# fan-shield.net
KiCad netlist of a schematic drawn in EAGLE
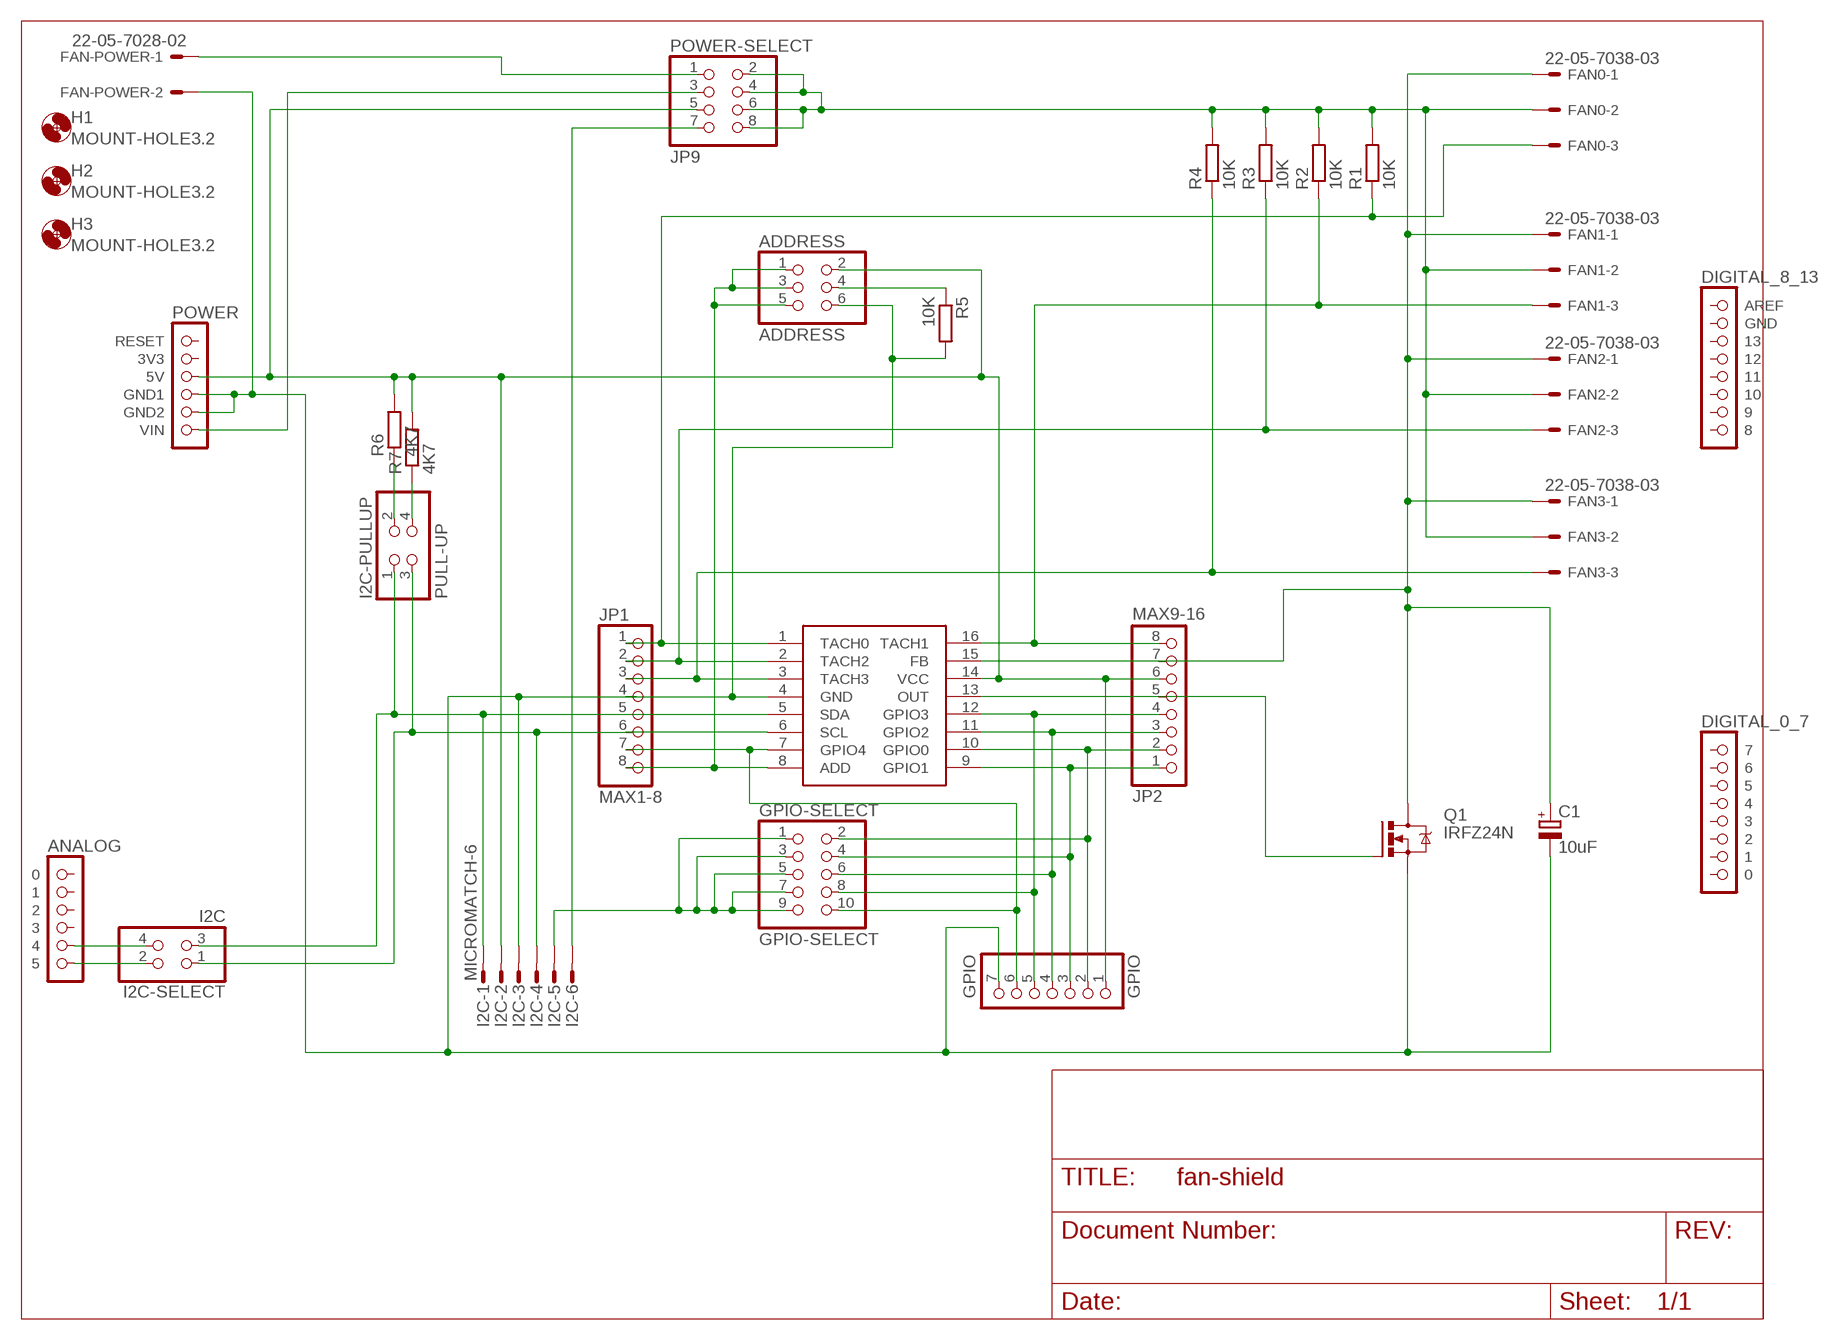
[diagram p0: schematic, sheet 1]

(export (version "E")
  (design (tool "Eeschema 10.0.6"))
  (components
    (comp (ref "ADDRESS")
      (value "ADDRESS")
      (footprint "eagle-import:2X03")
      (libsource (lib "eagle-import") (part "PINHD-2X3"))
    )
    (comp (ref "C1")
      (value "10uF")
      (footprint "eagle-import:E2,5-6")
      (libsource (lib "eagle-import") (part "CPOL-EUE2.5-6"))
    )
    (comp (ref "FAN-POWER")
      (value "22-05-7028-02")
      (footprint "eagle-import:7395-02")
      (libsource (lib "eagle-import") (part "22-?-0205-7028"))
    )
    (comp (ref "FAN0")
      (value "22-05-7038-03")
      (footprint "eagle-import:7395-03")
      (libsource (lib "eagle-import") (part "22-?-0305-7038"))
    )
    (comp (ref "FAN1")
      (value "22-05-7038-03")
      (footprint "eagle-import:7395-03")
      (libsource (lib "eagle-import") (part "22-?-0305-7038"))
    )
    (comp (ref "FAN2")
      (value "22-05-7038-03")
      (footprint "eagle-import:7395-03")
      (libsource (lib "eagle-import") (part "22-?-0305-7038"))
    )
    (comp (ref "FAN3")
      (value "22-05-7038-03")
      (footprint "eagle-import:7395-03")
      (libsource (lib "eagle-import") (part "22-?-0305-7038"))
    )
    (comp (ref "GPIO")
      (value "GPIO")
      (footprint "eagle-import:1X07_90")
      (libsource (lib "eagle-import") (part "PINHD-1X7/90"))
    )
    (comp (ref "GPIO-SELECT")
      (value "GPIO-SELECT")
      (footprint "eagle-import:2X05")
      (libsource (lib "eagle-import") (part "PINHD-2X5"))
    )
    (comp (ref "H1")
      (value "MOUNT-HOLE3.2")
      (footprint "eagle-import:3,2")
      (libsource (lib "eagle-import") (part "MOUNT-HOLE3.2"))
    )
    (comp (ref "H2")
      (value "MOUNT-HOLE3.2")
      (footprint "eagle-import:3,2")
      (libsource (lib "eagle-import") (part "MOUNT-HOLE3.2"))
    )
    (comp (ref "H3")
      (value "MOUNT-HOLE3.2")
      (footprint "eagle-import:3,2")
      (libsource (lib "eagle-import") (part "MOUNT-HOLE3.2"))
    )
    (comp (ref "I2C")
      (value "MICROMATCH-6")
      (footprint "eagle-import:MICROMATCH-6")
      (fields (field (name "MPN") "7-215464-6"))
      (libsource (lib "eagle-import") (part "MICROMATCH-6"))
    )
    (comp (ref "I2C-PULLUP")
      (value "PULL-UP")
      (footprint "eagle-import:2X02")
      (libsource (lib "eagle-import") (part "PINHD-2X2"))
    )
    (comp (ref "I2C-SELECT")
      (value "I2C")
      (footprint "eagle-import:2X02_90")
      (libsource (lib "eagle-import") (part "PINHD-2X2/90"))
    )
    (comp (ref "JP1")
      (value "MAX1-8")
      (footprint "eagle-import:1X08")
      (libsource (lib "eagle-import") (part "PINHD-1X8"))
    )
    (comp (ref "JP2")
      (value "MAX9-16")
      (footprint "eagle-import:1X08")
      (libsource (lib "eagle-import") (part "PINHD-1X8"))
    )
    (comp (ref "MAX6651")
      (value "MAX6651")
      (footprint "eagle-import:QSOP16")
      (libsource (lib "eagle-import") (part "MAX6651"))
    )
    (comp (ref "POWER-SELECT")
      (value "JP9")
      (footprint "eagle-import:2X04")
      (libsource (lib "eagle-import") (part "PINHD-2X4"))
    )
    (comp (ref "Q1")
      (value "IRFZ24N")
      (footprint "eagle-import:TO200AB")
      (libsource (lib "eagle-import") (part "IRFZ24N"))
    )
    (comp (ref "R1")
      (value "10K")
      (footprint "eagle-import:0207_10")
      (libsource (lib "eagle-import") (part "R-EU_0207/10"))
    )
    (comp (ref "R2")
      (value "10K")
      (footprint "eagle-import:0207_10")
      (libsource (lib "eagle-import") (part "R-EU_0207/10"))
    )
    (comp (ref "R3")
      (value "10K")
      (footprint "eagle-import:0207_10")
      (libsource (lib "eagle-import") (part "R-EU_0207/10"))
    )
    (comp (ref "R4")
      (value "10K")
      (footprint "eagle-import:0207_10")
      (libsource (lib "eagle-import") (part "R-EU_0207/10"))
    )
    (comp (ref "R5")
      (value "10K")
      (footprint "eagle-import:0207_10")
      (libsource (lib "eagle-import") (part "R-EU_0207/10"))
    )
    (comp (ref "R6")
      (value "4K7")
      (footprint "eagle-import:0207_10")
      (libsource (lib "eagle-import") (part "R-EU_0207/10"))
    )
    (comp (ref "R7")
      (value "4K7")
      (footprint "eagle-import:0207_10")
      (libsource (lib "eagle-import") (part "R-EU_0207/10"))
    )
    (comp (ref "U$1")
      (value "POWER")
      (footprint "eagle-import:1X06")
      (libsource (lib "eagle-import") (part "POWER"))
    )
    (comp (ref "U$2")
      (value "ANALOG")
      (footprint "eagle-import:1X06")
      (libsource (lib "eagle-import") (part "ANALOG"))
    )
    (comp (ref "U$3")
      (value "DIGITAL_0_7")
      (footprint "eagle-import:1X08")
      (libsource (lib "eagle-import") (part "DIGITAL_0_7"))
    )
    (comp (ref "U$4")
      (value "DIGITAL_8_13")
      (footprint "eagle-import:1X08")
      (libsource (lib "eagle-import") (part "DIGITAL_8_13"))
    )
  )
  (nets
    (net (code "1") (name "Net-(ADDRESS-Pad4)") (class "Default")
      (node (ref "ADDRESS") (pin "4") (pinfunction "4_4") (pintype "passive"))
      (node (ref "R5") (pin "1") (pinfunction "1_1") (pintype "passive"))
    )
    (net (code "2") (name "Net-(FAN-POWERA-S)") (class "Default")
      (node (ref "FAN-POWER") (pin "1") (pinfunction "S_1") (pintype "passive"))
      (node (ref "POWER-SELECT") (pin "1") (pinfunction "1_1") (pintype "passive"))
    )
    (net (code "3") (name "Net-(FAN-POWERB-S)") (class "Default")
      (node (ref "ADDRESS") (pin "6") (pinfunction "6_6") (pintype "passive"))
      (node (ref "C1") (pin "-") (pinfunction "-_-") (pintype "passive"))
      (node (ref "FAN-POWER") (pin "2") (pinfunction "S_2") (pintype "passive"))
      (node (ref "GPIO") (pin "7") (pinfunction "7_7") (pintype "passive"))
      (node (ref "I2C") (pin "3") (pinfunction "S_3") (pintype "passive"))
      (node (ref "JP1") (pin "4") (pinfunction "4_4") (pintype "passive"))
      (node (ref "MAX6651") (pin "4") (pinfunction "GND_4") (pintype "power_in"))
      (node (ref "Q1") (pin "S") (pinfunction "S_S") (pintype "passive"))
      (node (ref "R5") (pin "2") (pinfunction "2_2") (pintype "passive"))
      (node (ref "U$1") (pin "4") (pinfunction "GND1_4") (pintype "passive"))
      (node (ref "U$1") (pin "5") (pinfunction "GND2_5") (pintype "passive"))
    )
    (net (code "4") (name "Net-(FAN0A-S)") (class "Default")
      (node (ref "C1") (pin "+") (pinfunction "+_+") (pintype "passive"))
      (node (ref "FAN0") (pin "1") (pinfunction "S_1") (pintype "passive"))
      (node (ref "FAN1") (pin "1") (pinfunction "S_1") (pintype "passive"))
      (node (ref "FAN2") (pin "1") (pinfunction "S_1") (pintype "passive"))
      (node (ref "FAN3") (pin "1") (pinfunction "S_1") (pintype "passive"))
      (node (ref "JP2") (pin "7") (pinfunction "7_7") (pintype "passive"))
      (node (ref "MAX6651") (pin "15") (pinfunction "FB_15") (pintype "bidirectional"))
      (node (ref "Q1") (pin "D") (pinfunction "D_D") (pintype "passive"))
    )
    (net (code "5") (name "Net-(FAN0B-S)") (class "Default")
      (node (ref "FAN0") (pin "2") (pinfunction "S_2") (pintype "passive"))
      (node (ref "FAN1") (pin "2") (pinfunction "S_2") (pintype "passive"))
      (node (ref "FAN2") (pin "2") (pinfunction "S_2") (pintype "passive"))
      (node (ref "FAN3") (pin "2") (pinfunction "S_2") (pintype "passive"))
      (node (ref "POWER-SELECT") (pin "2") (pinfunction "2_2") (pintype "passive"))
      (node (ref "POWER-SELECT") (pin "4") (pinfunction "4_4") (pintype "passive"))
      (node (ref "POWER-SELECT") (pin "6") (pinfunction "6_6") (pintype "passive"))
      (node (ref "POWER-SELECT") (pin "8") (pinfunction "8_8") (pintype "passive"))
      (node (ref "R1") (pin "2") (pinfunction "2_2") (pintype "passive"))
      (node (ref "R2") (pin "2") (pinfunction "2_2") (pintype "passive"))
      (node (ref "R3") (pin "2") (pinfunction "2_2") (pintype "passive"))
      (node (ref "R4") (pin "2") (pinfunction "2_2") (pintype "passive"))
    )
    (net (code "6") (name "Net-(FAN0C-S)") (class "Default")
      (node (ref "FAN0") (pin "3") (pinfunction "S_3") (pintype "passive"))
      (node (ref "JP1") (pin "1") (pinfunction "1_1") (pintype "passive"))
      (node (ref "MAX6651") (pin "1") (pinfunction "TACH0_1") (pintype "input"))
      (node (ref "R1") (pin "1") (pinfunction "1_1") (pintype "passive"))
    )
    (net (code "7") (name "Net-(FAN1C-S)") (class "Default")
      (node (ref "FAN1") (pin "3") (pinfunction "S_3") (pintype "passive"))
      (node (ref "JP2") (pin "8") (pinfunction "8_8") (pintype "passive"))
      (node (ref "MAX6651") (pin "16") (pinfunction "TACH1_16") (pintype "input"))
      (node (ref "R2") (pin "1") (pinfunction "1_1") (pintype "passive"))
    )
    (net (code "8") (name "Net-(FAN2C-S)") (class "Default")
      (node (ref "FAN2") (pin "3") (pinfunction "S_3") (pintype "passive"))
      (node (ref "JP1") (pin "2") (pinfunction "2_2") (pintype "passive"))
      (node (ref "MAX6651") (pin "2") (pinfunction "TACH2_2") (pintype "input"))
      (node (ref "R3") (pin "1") (pinfunction "1_1") (pintype "passive"))
    )
    (net (code "9") (name "Net-(FAN3C-S)") (class "Default")
      (node (ref "FAN3") (pin "3") (pinfunction "S_3") (pintype "passive"))
      (node (ref "JP1") (pin "3") (pinfunction "3_3") (pintype "passive"))
      (node (ref "MAX6651") (pin "3") (pinfunction "TACH3_3") (pintype "input"))
      (node (ref "R4") (pin "1") (pinfunction "1_1") (pintype "passive"))
    )
    (net (code "10") (name "Net-(I2C-PULLUP-Pad2)") (class "Default")
      (node (ref "I2C-PULLUP") (pin "2") (pinfunction "2_2") (pintype "passive"))
      (node (ref "R6") (pin "1") (pinfunction "1_1") (pintype "passive"))
    )
    (net (code "11") (name "Net-(I2C-PULLUP-Pad4)") (class "Default")
      (node (ref "I2C-PULLUP") (pin "4") (pinfunction "4_4") (pintype "passive"))
      (node (ref "R7") (pin "1") (pinfunction "1_1") (pintype "passive"))
    )
    (net (code "12") (name "Net-(I2CA-S)") (class "Default")
      (node (ref "I2C") (pin "1") (pinfunction "S_1") (pintype "passive"))
      (node (ref "I2C-PULLUP") (pin "1") (pinfunction "1_1") (pintype "passive"))
      (node (ref "I2C-SELECT") (pin "3") (pinfunction "3_3") (pintype "passive"))
      (node (ref "JP1") (pin "5") (pinfunction "5_5") (pintype "passive"))
      (node (ref "MAX6651") (pin "5") (pinfunction "SDA_5") (pintype "bidirectional"))
    )
    (net (code "13") (name "Net-(I2CB-S)") (class "Default")
      (node (ref "ADDRESS") (pin "2") (pinfunction "2_2") (pintype "passive"))
      (node (ref "GPIO") (pin "1") (pinfunction "1_1") (pintype "passive"))
      (node (ref "I2C") (pin "2") (pinfunction "S_2") (pintype "passive"))
      (node (ref "JP2") (pin "6") (pinfunction "6_6") (pintype "passive"))
      (node (ref "MAX6651") (pin "14") (pinfunction "VCC_14") (pintype "bidirectional"))
      (node (ref "POWER-SELECT") (pin "5") (pinfunction "5_5") (pintype "passive"))
      (node (ref "R6") (pin "2") (pinfunction "2_2") (pintype "passive"))
      (node (ref "R7") (pin "2") (pinfunction "2_2") (pintype "passive"))
      (node (ref "U$1") (pin "3") (pinfunction "5V_3") (pintype "passive"))
    )
    (net (code "14") (name "Net-(I2CD-S)") (class "Default")
      (node (ref "I2C") (pin "4") (pinfunction "S_4") (pintype "passive"))
      (node (ref "I2C-PULLUP") (pin "3") (pinfunction "3_3") (pintype "passive"))
      (node (ref "I2C-SELECT") (pin "1") (pinfunction "1_1") (pintype "passive"))
      (node (ref "JP1") (pin "6") (pinfunction "6_6") (pintype "passive"))
      (node (ref "MAX6651") (pin "6") (pinfunction "SCL_6") (pintype "bidirectional"))
    )
    (net (code "15") (name "Net-(I2CE-S)") (class "Default")
      (node (ref "GPIO-SELECT") (pin "1") (pinfunction "1_1") (pintype "passive"))
      (node (ref "GPIO-SELECT") (pin "3") (pinfunction "3_3") (pintype "passive"))
      (node (ref "GPIO-SELECT") (pin "5") (pinfunction "5_5") (pintype "passive"))
      (node (ref "GPIO-SELECT") (pin "7") (pinfunction "7_7") (pintype "passive"))
      (node (ref "GPIO-SELECT") (pin "9") (pinfunction "9_9") (pintype "passive"))
      (node (ref "I2C") (pin "5") (pinfunction "S_5") (pintype "passive"))
    )
    (net (code "16") (name "Net-(I2CF-S)") (class "Default")
      (node (ref "I2C") (pin "6") (pinfunction "S_6") (pintype "passive"))
      (node (ref "POWER-SELECT") (pin "7") (pinfunction "7_7") (pintype "passive"))
    )
    (net (code "17") (name "Net-(MAX6651-ADD)") (class "Default")
      (node (ref "ADDRESS") (pin "1") (pinfunction "1_1") (pintype "passive"))
      (node (ref "ADDRESS") (pin "3") (pinfunction "3_3") (pintype "passive"))
      (node (ref "ADDRESS") (pin "5") (pinfunction "5_5") (pintype "passive"))
      (node (ref "JP1") (pin "8") (pinfunction "8_8") (pintype "passive"))
      (node (ref "MAX6651") (pin "8") (pinfunction "ADD_8") (pintype "bidirectional"))
    )
    (net (code "18") (name "Net-(MAX6651-GPIO0)") (class "Default")
      (node (ref "GPIO") (pin "2") (pinfunction "2_2") (pintype "passive"))
      (node (ref "GPIO-SELECT") (pin "2") (pinfunction "2_2") (pintype "passive"))
      (node (ref "JP2") (pin "2") (pinfunction "2_2") (pintype "passive"))
      (node (ref "MAX6651") (pin "10") (pinfunction "GPIO0_10") (pintype "bidirectional"))
    )
    (net (code "19") (name "Net-(MAX6651-GPIO1)") (class "Default")
      (node (ref "GPIO") (pin "3") (pinfunction "3_3") (pintype "passive"))
      (node (ref "GPIO-SELECT") (pin "4") (pinfunction "4_4") (pintype "passive"))
      (node (ref "JP2") (pin "1") (pinfunction "1_1") (pintype "passive"))
      (node (ref "MAX6651") (pin "9") (pinfunction "GPIO1_9") (pintype "bidirectional"))
    )
    (net (code "20") (name "Net-(MAX6651-GPIO2)") (class "Default")
      (node (ref "GPIO") (pin "4") (pinfunction "4_4") (pintype "passive"))
      (node (ref "GPIO-SELECT") (pin "6") (pinfunction "6_6") (pintype "passive"))
      (node (ref "JP2") (pin "3") (pinfunction "3_3") (pintype "passive"))
      (node (ref "MAX6651") (pin "11") (pinfunction "GPIO2_11") (pintype "bidirectional"))
    )
    (net (code "21") (name "Net-(MAX6651-GPIO3)") (class "Default")
      (node (ref "GPIO") (pin "5") (pinfunction "5_5") (pintype "passive"))
      (node (ref "GPIO-SELECT") (pin "8") (pinfunction "8_8") (pintype "passive"))
      (node (ref "JP2") (pin "4") (pinfunction "4_4") (pintype "passive"))
      (node (ref "MAX6651") (pin "12") (pinfunction "GPIO3_12") (pintype "bidirectional"))
    )
    (net (code "22") (name "Net-(MAX6651-GPIO4)") (class "Default")
      (node (ref "GPIO") (pin "6") (pinfunction "6_6") (pintype "passive"))
      (node (ref "GPIO-SELECT") (pin "10") (pinfunction "10_10") (pintype "passive"))
      (node (ref "JP1") (pin "7") (pinfunction "7_7") (pintype "passive"))
      (node (ref "MAX6651") (pin "7") (pinfunction "GPIO4_7") (pintype "bidirectional"))
    )
    (net (code "23") (name "Net-(MAX6651-OUT)") (class "Default")
      (node (ref "JP2") (pin "5") (pinfunction "5_5") (pintype "passive"))
      (node (ref "MAX6651") (pin "13") (pinfunction "OUT_13") (pintype "output"))
      (node (ref "Q1") (pin "G") (pinfunction "G_G") (pintype "passive"))
    )
    (net (code "24") (name "Net-(U$1-VIN)") (class "Default")
      (node (ref "POWER-SELECT") (pin "3") (pinfunction "3_3") (pintype "passive"))
      (node (ref "U$1") (pin "6") (pinfunction "VIN_6") (pintype "passive"))
    )
    (net (code "25") (name "Net-(U$2-4)") (class "Default")
      (node (ref "I2C-SELECT") (pin "4") (pinfunction "4_4") (pintype "passive"))
      (node (ref "U$2") (pin "5") (pinfunction "4_5") (pintype "passive"))
    )
    (net (code "26") (name "Net-(U$2-5)") (class "Default")
      (node (ref "I2C-SELECT") (pin "2") (pinfunction "2_2") (pintype "passive"))
      (node (ref "U$2") (pin "6") (pinfunction "5_6") (pintype "passive"))
    )
    (net (code "27") (name "unconnected-(U$1-3V3-Pad2)") (class "Default")
      (node (ref "U$1") (pin "2") (pinfunction "3V3_2") (pintype "passive"))
    )
    (net (code "28") (name "unconnected-(U$1-RESET-Pad1)") (class "Default")
      (node (ref "U$1") (pin "1") (pinfunction "RESET_1") (pintype "passive"))
    )
    (net (code "29") (name "unconnected-(U$2-0-Pad1)") (class "Default")
      (node (ref "U$2") (pin "1") (pinfunction "0_1") (pintype "passive"))
    )
    (net (code "30") (name "unconnected-(U$2-1-Pad2)") (class "Default")
      (node (ref "U$2") (pin "2") (pinfunction "1_2") (pintype "passive"))
    )
    (net (code "31") (name "unconnected-(U$2-2-Pad3)") (class "Default")
      (node (ref "U$2") (pin "3") (pinfunction "2_3") (pintype "passive"))
    )
    (net (code "32") (name "unconnected-(U$2-3-Pad4)") (class "Default")
      (node (ref "U$2") (pin "4") (pinfunction "3_4") (pintype "passive"))
    )
    (net (code "33") (name "unconnected-(U$3-0-Pad8)") (class "Default")
      (node (ref "U$3") (pin "8") (pinfunction "0_8") (pintype "passive"))
    )
    (net (code "34") (name "unconnected-(U$3-1-Pad7)") (class "Default")
      (node (ref "U$3") (pin "7") (pinfunction "1_7") (pintype "passive"))
    )
    (net (code "35") (name "unconnected-(U$3-2-Pad6)") (class "Default")
      (node (ref "U$3") (pin "6") (pinfunction "2_6") (pintype "passive"))
    )
    (net (code "36") (name "unconnected-(U$3-3-Pad5)") (class "Default")
      (node (ref "U$3") (pin "5") (pinfunction "3_5") (pintype "passive"))
    )
    (net (code "37") (name "unconnected-(U$3-5-Pad3)") (class "Default")
      (node (ref "U$3") (pin "3") (pinfunction "5_3") (pintype "passive"))
    )
    (net (code "38") (name "unconnected-(U$3-6-Pad2)") (class "Default")
      (node (ref "U$3") (pin "2") (pinfunction "6_2") (pintype "passive"))
    )
    (net (code "39") (name "unconnected-(U$3-7-Pad1)") (class "Default")
      (node (ref "U$3") (pin "1") (pinfunction "7_1") (pintype "passive"))
    )
    (net (code "40") (name "unconnected-(U$3-Pad4)") (class "Default")
      (node (ref "U$3") (pin "4") (pinfunction "4_4") (pintype "passive"))
    )
    (net (code "41") (name "unconnected-(U$4-9-Pad7)") (class "Default")
      (node (ref "U$4") (pin "7") (pinfunction "9_7") (pintype "passive"))
    )
    (net (code "42") (name "unconnected-(U$4-10-Pad6)") (class "Default")
      (node (ref "U$4") (pin "6") (pinfunction "10_6") (pintype "passive"))
    )
    (net (code "43") (name "unconnected-(U$4-11-Pad5)") (class "Default")
      (node (ref "U$4") (pin "5") (pinfunction "11_5") (pintype "passive"))
    )
    (net (code "44") (name "unconnected-(U$4-12-Pad4)") (class "Default")
      (node (ref "U$4") (pin "4") (pinfunction "12_4") (pintype "passive"))
    )
    (net (code "45") (name "unconnected-(U$4-13-Pad3)") (class "Default")
      (node (ref "U$4") (pin "3") (pinfunction "13_3") (pintype "passive"))
    )
    (net (code "46") (name "unconnected-(U$4-AREF-Pad1)") (class "Default")
      (node (ref "U$4") (pin "1") (pinfunction "AREF_1") (pintype "passive"))
    )
    (net (code "47") (name "unconnected-(U$4-GND-Pad2)") (class "Default")
      (node (ref "U$4") (pin "2") (pinfunction "GND_2") (pintype "passive"))
    )
    (net (code "48") (name "unconnected-(U$4-Pad8)") (class "Default")
      (node (ref "U$4") (pin "8") (pinfunction "8_8") (pintype "passive"))
    )
  )
)
